# FRONT_PL.net
KiCad netlist of a schematic drawn in Altium Designer
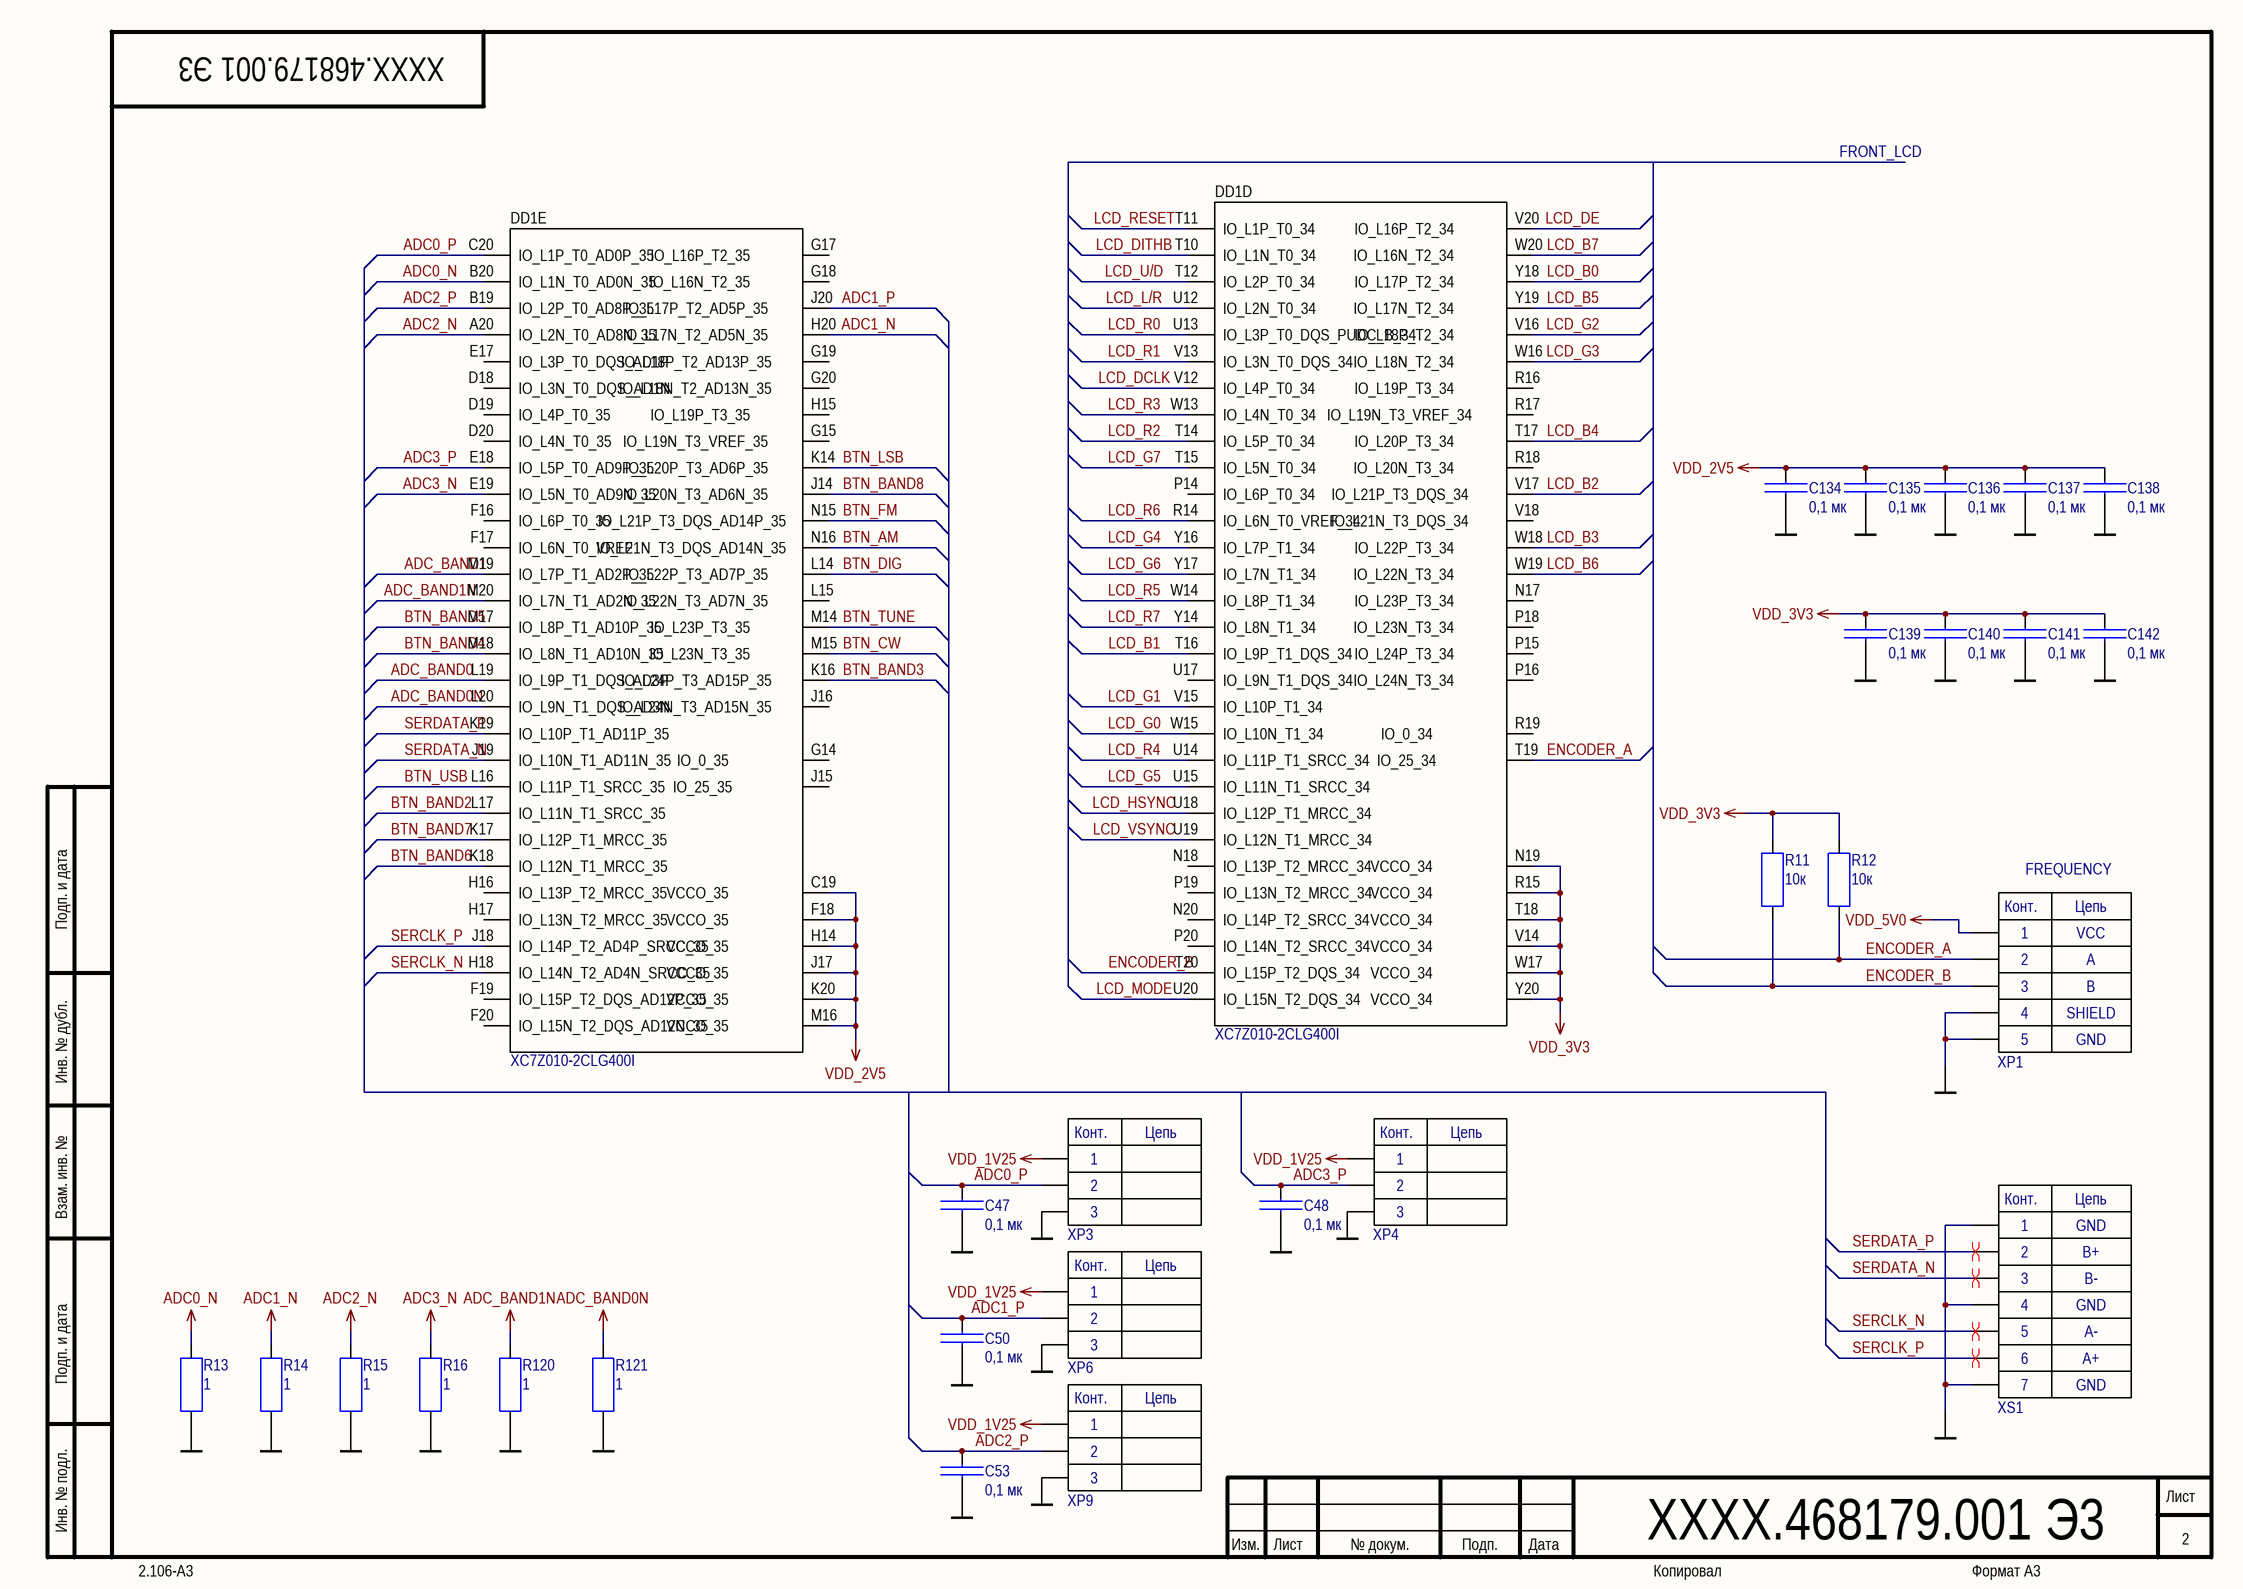
[diagram p0: FRONT_PL.SchDoc]

(export (version "E")
  (design (tool "Eeschema 10.0.6"))
  (components
    (comp (ref "C47")
      (value "CC0402KRX5R6BB104")
      (footprint "CAPC1005X05L")
      (description "ЧИП конденсатор")
      (fields
        (field (name "NOMINAL") "0,1 мк")
        (field (name "MANUFACTURER") "Yageo")
        (field (name "TOLERANCE") "10%")
      )
      (libsource (lib "Database_Gost") (part "Capacitor const"))
    )
    (comp (ref "C48")
      (value "CC0402KRX5R6BB104")
      (footprint "CAPC1005X05L")
      (description "ЧИП конденсатор")
      (fields
        (field (name "NOMINAL") "0,1 мк")
        (field (name "MANUFACTURER") "Yageo")
        (field (name "TOLERANCE") "10%")
      )
      (libsource (lib "Database_Gost") (part "Capacitor const"))
    )
    (comp (ref "C50")
      (value "CC0402KRX5R6BB104")
      (footprint "CAPC1005X05L")
      (description "ЧИП конденсатор")
      (fields
        (field (name "NOMINAL") "0,1 мк")
        (field (name "MANUFACTURER") "Yageo")
        (field (name "TOLERANCE") "10%")
      )
      (libsource (lib "Database_Gost") (part "Capacitor const"))
    )
    (comp (ref "C53")
      (value "CC0402KRX5R6BB104")
      (footprint "CAPC1005X05L")
      (description "ЧИП конденсатор")
      (fields
        (field (name "NOMINAL") "0,1 мк")
        (field (name "MANUFACTURER") "Yageo")
        (field (name "TOLERANCE") "10%")
      )
      (libsource (lib "Database_Gost") (part "Capacitor const"))
    )
    (comp (ref "C134")
      (value "CC0402KRX5R6BB104")
      (footprint "CAPC1005X05L")
      (description "ЧИП конденсатор")
      (fields
        (field (name "NOMINAL") "0,1 мк")
        (field (name "MANUFACTURER") "Yageo")
        (field (name "TOLERANCE") "10%")
      )
      (libsource (lib "Database_Gost") (part "Capacitor const"))
    )
    (comp (ref "C135")
      (value "CC0402KRX5R6BB104")
      (footprint "CAPC1005X05L")
      (description "ЧИП конденсатор")
      (fields
        (field (name "NOMINAL") "0,1 мк")
        (field (name "MANUFACTURER") "Yageo")
        (field (name "TOLERANCE") "10%")
      )
      (libsource (lib "Database_Gost") (part "Capacitor const"))
    )
    (comp (ref "C136")
      (value "CC0402KRX5R6BB104")
      (footprint "CAPC1005X05L")
      (description "ЧИП конденсатор")
      (fields
        (field (name "NOMINAL") "0,1 мк")
        (field (name "MANUFACTURER") "Yageo")
        (field (name "TOLERANCE") "10%")
      )
      (libsource (lib "Database_Gost") (part "Capacitor const"))
    )
    (comp (ref "C137")
      (value "CC0402KRX5R6BB104")
      (footprint "CAPC1005X05L")
      (description "ЧИП конденсатор")
      (fields
        (field (name "NOMINAL") "0,1 мк")
        (field (name "MANUFACTURER") "Yageo")
        (field (name "TOLERANCE") "10%")
      )
      (libsource (lib "Database_Gost") (part "Capacitor const"))
    )
    (comp (ref "C138")
      (value "CC0402KRX5R6BB104")
      (footprint "CAPC1005X05L")
      (description "ЧИП конденсатор")
      (fields
        (field (name "NOMINAL") "0,1 мк")
        (field (name "MANUFACTURER") "Yageo")
        (field (name "TOLERANCE") "10%")
      )
      (libsource (lib "Database_Gost") (part "Capacitor const"))
    )
    (comp (ref "C139")
      (value "CC0402KRX5R6BB104")
      (footprint "CAPC1005X05L")
      (description "ЧИП конденсатор")
      (fields
        (field (name "NOMINAL") "0,1 мк")
        (field (name "MANUFACTURER") "Yageo")
        (field (name "TOLERANCE") "10%")
      )
      (libsource (lib "Database_Gost") (part "Capacitor const"))
    )
    (comp (ref "C140")
      (value "CC0402KRX5R6BB104")
      (footprint "CAPC1005X05L")
      (description "ЧИП конденсатор")
      (fields
        (field (name "NOMINAL") "0,1 мк")
        (field (name "MANUFACTURER") "Yageo")
        (field (name "TOLERANCE") "10%")
      )
      (libsource (lib "Database_Gost") (part "Capacitor const"))
    )
    (comp (ref "C141")
      (value "CC0402KRX5R6BB104")
      (footprint "CAPC1005X05L")
      (description "ЧИП конденсатор")
      (fields
        (field (name "NOMINAL") "0,1 мк")
        (field (name "MANUFACTURER") "Yageo")
        (field (name "TOLERANCE") "10%")
      )
      (libsource (lib "Database_Gost") (part "Capacitor const"))
    )
    (comp (ref "C142")
      (value "CC0402KRX5R6BB104")
      (footprint "CAPC1005X05L")
      (description "ЧИП конденсатор")
      (fields
        (field (name "NOMINAL") "0,1 мк")
        (field (name "MANUFACTURER") "Yageo")
        (field (name "TOLERANCE") "10%")
      )
      (libsource (lib "Database_Gost") (part "Capacitor const"))
    )
    (comp (ref "DD1")
      (value "XC7Z010-2CLG400I")
      (footprint "BGA400C80P20X20_1700X1700X147")
      (description "Zynq®-7000 SoC Family")
      (fields (field (name "MANUFACTURER") "Xilinx"))
      (libsource (lib "Chips_single") (part "XC7Z010-2CLG400I"))
    )
    (comp (ref "R11")
      (value "RC0402JR-0710KL")
      (footprint "RESC1005X04L")
      (description "ЧИП резистор")
      (fields
        (field (name "NOMINAL") "10к")
        (field (name "MANUFACTURER") "Yageo")
        (field (name "TOLERANCE") "5%")
      )
      (libsource (lib "Database_Gost") (part "Resistor const"))
    )
    (comp (ref "R12")
      (value "RC0402JR-0710KL")
      (footprint "RESC1005X04L")
      (description "ЧИП резистор")
      (fields
        (field (name "NOMINAL") "10к")
        (field (name "MANUFACTURER") "Yageo")
        (field (name "TOLERANCE") "5%")
      )
      (libsource (lib "Database_Gost") (part "Resistor const"))
    )
    (comp (ref "R13")
      (value "RC0402JR-071RL")
      (footprint "RESC1005X04L")
      (description "ЧИП резистор")
      (fields
        (field (name "NOMINAL") "1")
        (field (name "MANUFACTURER") "Yageo")
        (field (name "TOLERANCE") "5%")
      )
      (libsource (lib "Database_Gost") (part "Resistor const"))
    )
    (comp (ref "R14")
      (value "RC0402JR-071RL")
      (footprint "RESC1005X04L")
      (description "ЧИП резистор")
      (fields
        (field (name "NOMINAL") "1")
        (field (name "MANUFACTURER") "Yageo")
        (field (name "TOLERANCE") "5%")
      )
      (libsource (lib "Database_Gost") (part "Resistor const"))
    )
    (comp (ref "R15")
      (value "RC0402JR-071RL")
      (footprint "RESC1005X04L")
      (description "ЧИП резистор")
      (fields
        (field (name "NOMINAL") "1")
        (field (name "MANUFACTURER") "Yageo")
        (field (name "TOLERANCE") "5%")
      )
      (libsource (lib "Database_Gost") (part "Resistor const"))
    )
    (comp (ref "R16")
      (value "RC0402JR-071RL")
      (footprint "RESC1005X04L")
      (description "ЧИП резистор")
      (fields
        (field (name "NOMINAL") "1")
        (field (name "MANUFACTURER") "Yageo")
        (field (name "TOLERANCE") "5%")
      )
      (libsource (lib "Database_Gost") (part "Resistor const"))
    )
    (comp (ref "R120")
      (value "RC0402JR-071RL")
      (footprint "RESC1005X04L")
      (description "ЧИП резистор")
      (fields
        (field (name "NOMINAL") "1")
        (field (name "MANUFACTURER") "Yageo")
        (field (name "TOLERANCE") "5%")
      )
      (libsource (lib "Database_Gost") (part "Resistor const"))
    )
    (comp (ref "R121")
      (value "RC0402JR-071RL")
      (footprint "RESC1005X04L")
      (description "ЧИП резистор")
      (fields
        (field (name "NOMINAL") "1")
        (field (name "MANUFACTURER") "Yageo")
        (field (name "TOLERANCE") "5%")
      )
      (libsource (lib "Database_Gost") (part "Resistor const"))
    )
    (comp (ref "XP1")
      (value "WB-05")
      (footprint "WB-05 (MW-5M) pitch 2.00mm")
      (description "WB-05 (MW-5M) pitch 2.00mm\r\nDS1066-05M")
      (libsource (lib "Connectors") (part "WB-05"))
    )
    (comp (ref "XP3")
      (value "WB-03")
      (footprint "WB-03 (MW-3M) PITCH 2.00MM")
      (description "WB-03(MW-3M) pitch 2.00mm\r\nDS1066-03M")
      (libsource (lib "Connectors") (part "WB-03"))
    )
    (comp (ref "XP4")
      (value "WB-03")
      (footprint "WB-03 (MW-3M) PITCH 2.00MM")
      (description "WB-03(MW-3M) pitch 2.00mm\r\nDS1066-03M")
      (libsource (lib "Connectors") (part "WB-03"))
    )
    (comp (ref "XP6")
      (value "WB-03")
      (footprint "WB-03 (MW-3M) PITCH 2.00MM")
      (description "WB-03(MW-3M) pitch 2.00mm\r\nDS1066-03M")
      (libsource (lib "Connectors") (part "WB-03"))
    )
    (comp (ref "XP9")
      (value "WB-03")
      (footprint "WB-03 (MW-3M) PITCH 2.00MM")
      (description "WB-03(MW-3M) pitch 2.00mm\r\nDS1066-03M")
      (libsource (lib "Connectors") (part "WB-03"))
    )
    (comp (ref "XS1")
      (value "KLS1-SATA001")
      (footprint "KLS1-SATA001")
      (description "SATA Type A 7P Male Connector,SMD")
      (libsource (lib "Connectors") (part "SATA KLS1-SATA001"))
    )
  )
  (nets
    (net (code "1") (name "/ADC0_P") (class "Default")
      (node (ref "C47") (pin "2") (pinfunction "2_2") (pintype "passive"))
      (node (ref "DD1") (pin "C20") (pinfunction "IO_L1P_T0_AD0P_35_C20") (pintype "passive"))
      (node (ref "XP3") (pin "2") (pinfunction "2_2") (pintype "passive"))
    )
    (net (code "2") (name "/ADC1_P") (class "Default")
      (node (ref "C50") (pin "2") (pinfunction "2_2") (pintype "passive"))
      (node (ref "DD1") (pin "J20") (pinfunction "IO_L17P_T2_AD5P_35_J20") (pintype "passive"))
      (node (ref "XP6") (pin "2") (pinfunction "2_2") (pintype "passive"))
    )
    (net (code "3") (name "/ADC2_P") (class "Default")
      (node (ref "C53") (pin "2") (pinfunction "2_2") (pintype "passive"))
      (node (ref "DD1") (pin "B19") (pinfunction "IO_L2P_T0_AD8P_35_B19") (pintype "passive"))
      (node (ref "XP9") (pin "2") (pinfunction "2_2") (pintype "passive"))
    )
    (net (code "4") (name "/ADC3_P") (class "Default")
      (node (ref "C48") (pin "2") (pinfunction "2_2") (pintype "passive"))
      (node (ref "DD1") (pin "E18") (pinfunction "IO_L5P_T0_AD9P_35_E18") (pintype "passive"))
      (node (ref "XP4") (pin "2") (pinfunction "2_2") (pintype "passive"))
    )
    (net (code "5") (name "/ADC_BAND0") (class "Default")
      (node (ref "DD1") (pin "L19") (pinfunction "IO_L9P_T1_DQS_AD3P_L19") (pintype "passive"))
    )
    (net (code "6") (name "/ADC_BAND1") (class "Default")
      (node (ref "DD1") (pin "M19") (pinfunction "IO_L7P_T1_AD2P_35_M19") (pintype "passive"))
    )
    (net (code "7") (name "/BTN_AM") (class "Default")
      (node (ref "DD1") (pin "N16") (pinfunction "IO_L21N_T3_DQS_AD14N_35_N16") (pintype "passive"))
    )
    (net (code "8") (name "/BTN_BAND2") (class "Default")
      (node (ref "DD1") (pin "L17") (pinfunction "IO_L11N_T1_SRCC_35_L17") (pintype "passive"))
    )
    (net (code "9") (name "/BTN_BAND3") (class "Default")
      (node (ref "DD1") (pin "K16") (pinfunction "IO_L24P_T3_AD15P_35_K16") (pintype "passive"))
    )
    (net (code "10") (name "/BTN_BAND4") (class "Default")
      (node (ref "DD1") (pin "M18") (pinfunction "IO_L8N_T1_AD10N_35_M18") (pintype "passive"))
    )
    (net (code "11") (name "/BTN_BAND5") (class "Default")
      (node (ref "DD1") (pin "M17") (pinfunction "IO_L8P_T1_AD10P_35_M17") (pintype "passive"))
    )
    (net (code "12") (name "/BTN_BAND6") (class "Default")
      (node (ref "DD1") (pin "K18") (pinfunction "IO_L12N_T1_MRCC_35_K18") (pintype "passive"))
    )
    (net (code "13") (name "/BTN_BAND7") (class "Default")
      (node (ref "DD1") (pin "K17") (pinfunction "IO_L12P_T1_MRCC_35_K17") (pintype "passive"))
    )
    (net (code "14") (name "/BTN_BAND8") (class "Default")
      (node (ref "DD1") (pin "J14") (pinfunction "IO_L20N_T3_AD6N_35_J14") (pintype "passive"))
    )
    (net (code "15") (name "/BTN_CW") (class "Default")
      (node (ref "DD1") (pin "M15") (pinfunction "IO_L23N_T3_35_M15") (pintype "passive"))
    )
    (net (code "16") (name "/BTN_DIG") (class "Default")
      (node (ref "DD1") (pin "L14") (pinfunction "IO_L22P_T3_AD7P_35_L14") (pintype "passive"))
    )
    (net (code "17") (name "/BTN_FM") (class "Default")
      (node (ref "DD1") (pin "N15") (pinfunction "IO_L21P_T3_DQS_AD14P_35_N15") (pintype "passive"))
    )
    (net (code "18") (name "/BTN_LSB") (class "Default")
      (node (ref "DD1") (pin "K14") (pinfunction "IO_L20P_T3_AD6P_35_K14") (pintype "passive"))
    )
    (net (code "19") (name "/BTN_TUNE") (class "Default")
      (node (ref "DD1") (pin "M14") (pinfunction "IO_L23P_T3_35_M14") (pintype "passive"))
    )
    (net (code "20") (name "/BTN_USB") (class "Default")
      (node (ref "DD1") (pin "L16") (pinfunction "IO_L11P_T1_SRCC_35_L16") (pintype "passive"))
    )
    (net (code "21") (name "/ENCODER_A") (class "Default")
      (node (ref "DD1") (pin "T19") (pinfunction "IO_25_34_T19") (pintype "open_collector"))
      (node (ref "R12") (pin "2") (pinfunction "2_2") (pintype "passive"))
      (node (ref "XP1") (pin "2") (pinfunction "2_2") (pintype "passive"))
    )
    (net (code "22") (name "/ENCODER_B") (class "Default")
      (node (ref "DD1") (pin "T20") (pinfunction "IO_L15P_T2_DQS_34_T20") (pintype "open_collector"))
      (node (ref "R11") (pin "2") (pinfunction "2_2") (pintype "passive"))
      (node (ref "XP1") (pin "3") (pinfunction "3_3") (pintype "passive"))
    )
    (net (code "23") (name "/LCD_B0") (class "Default")
      (node (ref "DD1") (pin "Y18") (pinfunction "IO_L17P_T2_34_Y18") (pintype "open_collector"))
    )
    (net (code "24") (name "/LCD_B1") (class "Default")
      (node (ref "DD1") (pin "T16") (pinfunction "IO_L9P_T1_DQS_34_T16") (pintype "open_collector"))
    )
    (net (code "25") (name "/LCD_B2") (class "Default")
      (node (ref "DD1") (pin "V17") (pinfunction "IO_L21P_T3_DQS_34_V17") (pintype "open_collector"))
    )
    (net (code "26") (name "/LCD_B3") (class "Default")
      (node (ref "DD1") (pin "W18") (pinfunction "IO_L22P_T3_34_W18") (pintype "open_collector"))
    )
    (net (code "27") (name "/LCD_B4") (class "Default")
      (node (ref "DD1") (pin "T17") (pinfunction "IO_L20P_T3_34_T17") (pintype "open_collector"))
    )
    (net (code "28") (name "/LCD_B5") (class "Default")
      (node (ref "DD1") (pin "Y19") (pinfunction "IO_L17N_T2_34_Y19") (pintype "open_collector"))
    )
    (net (code "29") (name "/LCD_B6") (class "Default")
      (node (ref "DD1") (pin "W19") (pinfunction "IO_L22N_T3_34_W19") (pintype "open_collector"))
    )
    (net (code "30") (name "/LCD_B7") (class "Default")
      (node (ref "DD1") (pin "W20") (pinfunction "IO_L16N_T2_34_W20") (pintype "open_collector"))
    )
    (net (code "31") (name "/LCD_DCLK") (class "Default")
      (node (ref "DD1") (pin "V12") (pinfunction "IO_L4P_T0_34_V12") (pintype "open_collector"))
    )
    (net (code "32") (name "/LCD_DE") (class "Default")
      (node (ref "DD1") (pin "V20") (pinfunction "IO_L16P_T2_34_V20") (pintype "open_collector"))
    )
    (net (code "33") (name "/LCD_DITHB") (class "Default")
      (node (ref "DD1") (pin "T10") (pinfunction "IO_L1N_T0_34_T10") (pintype "open_collector"))
    )
    (net (code "34") (name "/LCD_G0") (class "Default")
      (node (ref "DD1") (pin "W15") (pinfunction "IO_L10N_T1_34_W15") (pintype "open_collector"))
    )
    (net (code "35") (name "/LCD_G1") (class "Default")
      (node (ref "DD1") (pin "V15") (pinfunction "IO_L10P_T1_34_V15") (pintype "open_collector"))
    )
    (net (code "36") (name "/LCD_G2") (class "Default")
      (node (ref "DD1") (pin "V16") (pinfunction "IO_L18P_T2_34_V16") (pintype "open_collector"))
    )
    (net (code "37") (name "/LCD_G3") (class "Default")
      (node (ref "DD1") (pin "W16") (pinfunction "IO_L18N_T2_34_W16") (pintype "open_collector"))
    )
    (net (code "38") (name "/LCD_G4") (class "Default")
      (node (ref "DD1") (pin "Y16") (pinfunction "IO_L7P_T1_34_Y16") (pintype "open_collector"))
    )
    (net (code "39") (name "/LCD_G5") (class "Default")
      (node (ref "DD1") (pin "U15") (pinfunction "IO_L11N_T1_SRCC_34_U15") (pintype "open_collector"))
    )
    (net (code "40") (name "/LCD_G6") (class "Default")
      (node (ref "DD1") (pin "Y17") (pinfunction "IO_L7N_T1_34_Y17") (pintype "open_collector"))
    )
    (net (code "41") (name "/LCD_G7") (class "Default")
      (node (ref "DD1") (pin "T15") (pinfunction "IO_L5N_T0_34_T15") (pintype "open_collector"))
    )
    (net (code "42") (name "/LCD_HSYNC") (class "Default")
      (node (ref "DD1") (pin "U18") (pinfunction "IO_L12P_T1_MRCC_34_U18") (pintype "open_collector"))
    )
    (net (code "43") (name "/LCD_L{slash}R") (class "Default")
      (node (ref "DD1") (pin "U12") (pinfunction "IO_L2N_T0_34_U12") (pintype "open_collector"))
    )
    (net (code "44") (name "/LCD_MODE") (class "Default")
      (node (ref "DD1") (pin "U20") (pinfunction "IO_L15N_T2_DQS_34_U20") (pintype "open_collector"))
    )
    (net (code "45") (name "/LCD_R0") (class "Default")
      (node (ref "DD1") (pin "U13") (pinfunction "IO_L3P_T0_DQS_PUDC_B_34_U13") (pintype "open_collector"))
    )
    (net (code "46") (name "/LCD_R1") (class "Default")
      (node (ref "DD1") (pin "V13") (pinfunction "IO_L3N_T0_DQS_34_V13") (pintype "open_collector"))
    )
    (net (code "47") (name "/LCD_R2") (class "Default")
      (node (ref "DD1") (pin "T14") (pinfunction "IO_L5P_T0_34_T14") (pintype "open_collector"))
    )
    (net (code "48") (name "/LCD_R3") (class "Default")
      (node (ref "DD1") (pin "W13") (pinfunction "IO_L4N_T0_34_W13") (pintype "open_collector"))
    )
    (net (code "49") (name "/LCD_R4") (class "Default")
      (node (ref "DD1") (pin "U14") (pinfunction "IO_L11P_T1_SRCC_34_U14") (pintype "open_collector"))
    )
    (net (code "50") (name "/LCD_R5") (class "Default")
      (node (ref "DD1") (pin "W14") (pinfunction "IO_L8P_T1_34_W14") (pintype "open_collector"))
    )
    (net (code "51") (name "/LCD_R6") (class "Default")
      (node (ref "DD1") (pin "R14") (pinfunction "IO_L6N_T0_VREF_34_R14") (pintype "open_collector"))
    )
    (net (code "52") (name "/LCD_R7") (class "Default")
      (node (ref "DD1") (pin "Y14") (pinfunction "IO_L8N_T1_34_Y14") (pintype "open_collector"))
    )
    (net (code "53") (name "/LCD_RESET") (class "Default")
      (node (ref "DD1") (pin "T11") (pinfunction "IO_L1P_T0_34_T11") (pintype "open_collector"))
    )
    (net (code "54") (name "/LCD_U{slash}D") (class "Default")
      (node (ref "DD1") (pin "T12") (pinfunction "IO_L2P_T0_34_T12") (pintype "open_collector"))
    )
    (net (code "55") (name "/LCD_VSYNC") (class "Default")
      (node (ref "DD1") (pin "U19") (pinfunction "IO_L12N_T1_MRCC_34_U19") (pintype "open_collector"))
    )
    (net (code "56") (name "/SERCLK_N") (class "Default")
      (node (ref "DD1") (pin "H18") (pinfunction "IO_L14N_T2_AD4N_SRCC_35_H18") (pintype "passive"))
      (node (ref "XS1") (pin "5") (pinfunction "5_5") (pintype "passive"))
    )
    (net (code "57") (name "/SERCLK_P") (class "Default")
      (node (ref "DD1") (pin "J18") (pinfunction "IO_L14P_T2_AD4P_SRCC_35_J18") (pintype "passive"))
      (node (ref "XS1") (pin "6") (pinfunction "6_6") (pintype "passive"))
    )
    (net (code "58") (name "/SERDATA_N") (class "Default")
      (node (ref "DD1") (pin "J19") (pinfunction "IO_L10N_T1_AD11N_35_J19") (pintype "passive"))
      (node (ref "XS1") (pin "3") (pinfunction "3_3") (pintype "passive"))
    )
    (net (code "59") (name "/SERDATA_P") (class "Default")
      (node (ref "DD1") (pin "K19") (pinfunction "IO_L10P_T1_AD11P_35_K19") (pintype "passive"))
      (node (ref "XS1") (pin "2") (pinfunction "2_2") (pintype "passive"))
    )
    (net (code "60") (name "ADC0_N") (class "Default")
      (node (ref "DD1") (pin "B20") (pinfunction "IO_L1N_T0_AD0N_35_B20") (pintype "passive"))
      (node (ref "R13") (pin "2") (pinfunction "2_2") (pintype "passive"))
    )
    (net (code "61") (name "ADC1_N") (class "Default")
      (node (ref "DD1") (pin "H20") (pinfunction "IO_L17N_T2_AD5N_35_H20") (pintype "passive"))
      (node (ref "R14") (pin "2") (pinfunction "2_2") (pintype "passive"))
    )
    (net (code "62") (name "ADC2_N") (class "Default")
      (node (ref "DD1") (pin "A20") (pinfunction "IO_L2N_T0_AD8N_35_A20") (pintype "passive"))
      (node (ref "R15") (pin "2") (pinfunction "2_2") (pintype "passive"))
    )
    (net (code "63") (name "ADC3_N") (class "Default")
      (node (ref "DD1") (pin "E19") (pinfunction "IO_L5N_T0_AD9N_35_E19") (pintype "passive"))
      (node (ref "R16") (pin "2") (pinfunction "2_2") (pintype "passive"))
    )
    (net (code "64") (name "ADC_BAND0N") (class "Default")
      (node (ref "DD1") (pin "L20") (pinfunction "IO_L9N_T1_DQS_AD3N_L20") (pintype "passive"))
      (node (ref "R121") (pin "2") (pinfunction "2_2") (pintype "passive"))
    )
    (net (code "65") (name "ADC_BAND1N") (class "Default")
      (node (ref "DD1") (pin "M20") (pinfunction "IO_L7N_T1_AD2N_35_M20") (pintype "passive"))
      (node (ref "R120") (pin "2") (pinfunction "2_2") (pintype "passive"))
    )
    (net (code "66") (name "GND") (class "Default")
      (node (ref "C134") (pin "1") (pinfunction "1_1") (pintype "passive"))
      (node (ref "C135") (pin "1") (pinfunction "1_1") (pintype "passive"))
      (node (ref "C136") (pin "1") (pinfunction "1_1") (pintype "passive"))
      (node (ref "C137") (pin "1") (pinfunction "1_1") (pintype "passive"))
      (node (ref "C138") (pin "1") (pinfunction "1_1") (pintype "passive"))
      (node (ref "C139") (pin "1") (pinfunction "1_1") (pintype "passive"))
      (node (ref "C140") (pin "1") (pinfunction "1_1") (pintype "passive"))
      (node (ref "C141") (pin "1") (pinfunction "1_1") (pintype "passive"))
      (node (ref "C142") (pin "1") (pinfunction "1_1") (pintype "passive"))
      (node (ref "C47") (pin "1") (pinfunction "1_1") (pintype "passive"))
      (node (ref "C48") (pin "1") (pinfunction "1_1") (pintype "passive"))
      (node (ref "C50") (pin "1") (pinfunction "1_1") (pintype "passive"))
      (node (ref "C53") (pin "1") (pinfunction "1_1") (pintype "passive"))
      (node (ref "R120") (pin "1") (pinfunction "1_1") (pintype "passive"))
      (node (ref "R121") (pin "1") (pinfunction "1_1") (pintype "passive"))
      (node (ref "R13") (pin "1") (pinfunction "1_1") (pintype "passive"))
      (node (ref "R14") (pin "1") (pinfunction "1_1") (pintype "passive"))
      (node (ref "R15") (pin "1") (pinfunction "1_1") (pintype "passive"))
      (node (ref "R16") (pin "1") (pinfunction "1_1") (pintype "passive"))
      (node (ref "XP1") (pin "4") (pinfunction "4_4") (pintype "passive"))
      (node (ref "XP1") (pin "5") (pinfunction "5_5") (pintype "passive"))
      (node (ref "XP3") (pin "3") (pinfunction "3_3") (pintype "passive"))
      (node (ref "XP4") (pin "3") (pinfunction "3_3") (pintype "passive"))
      (node (ref "XP6") (pin "3") (pinfunction "3_3") (pintype "passive"))
      (node (ref "XP9") (pin "3") (pinfunction "3_3") (pintype "passive"))
      (node (ref "XS1") (pin "1") (pinfunction "1_1") (pintype "passive"))
      (node (ref "XS1") (pin "4") (pinfunction "4_4") (pintype "passive"))
      (node (ref "XS1") (pin "7") (pinfunction "7_7") (pintype "passive"))
    )
    (net (code "67") (name "VDD_1V25") (class "Default")
      (node (ref "XP3") (pin "1") (pinfunction "1_1") (pintype "passive"))
      (node (ref "XP4") (pin "1") (pinfunction "1_1") (pintype "passive"))
      (node (ref "XP6") (pin "1") (pinfunction "1_1") (pintype "passive"))
      (node (ref "XP9") (pin "1") (pinfunction "1_1") (pintype "passive"))
    )
    (net (code "68") (name "VDD_2V5") (class "Default")
      (node (ref "C134") (pin "2") (pinfunction "2_2") (pintype "passive"))
      (node (ref "C135") (pin "2") (pinfunction "2_2") (pintype "passive"))
      (node (ref "C136") (pin "2") (pinfunction "2_2") (pintype "passive"))
      (node (ref "C137") (pin "2") (pinfunction "2_2") (pintype "passive"))
      (node (ref "C138") (pin "2") (pinfunction "2_2") (pintype "passive"))
      (node (ref "DD1") (pin "C19") (pinfunction "VCCO_35_C19") (pintype "passive"))
      (node (ref "DD1") (pin "F18") (pinfunction "VCCO_35_F18") (pintype "passive"))
      (node (ref "DD1") (pin "H14") (pinfunction "VCCO_35_H14") (pintype "passive"))
      (node (ref "DD1") (pin "J17") (pinfunction "VCCO_35_J17") (pintype "passive"))
      (node (ref "DD1") (pin "K20") (pinfunction "VCCO_35_K20") (pintype "passive"))
      (node (ref "DD1") (pin "M16") (pinfunction "VCCO_35_M16") (pintype "passive"))
    )
    (net (code "69") (name "VDD_3V3") (class "Default")
      (node (ref "C139") (pin "2") (pinfunction "2_2") (pintype "passive"))
      (node (ref "C140") (pin "2") (pinfunction "2_2") (pintype "passive"))
      (node (ref "C141") (pin "2") (pinfunction "2_2") (pintype "passive"))
      (node (ref "C142") (pin "2") (pinfunction "2_2") (pintype "passive"))
      (node (ref "DD1") (pin "N19") (pinfunction "VCCO_34_N19") (pintype "open_collector"))
      (node (ref "DD1") (pin "R15") (pinfunction "VCCO_34_R15") (pintype "open_collector"))
      (node (ref "DD1") (pin "T18") (pinfunction "VCCO_34_T18") (pintype "open_collector"))
      (node (ref "DD1") (pin "V14") (pinfunction "VCCO_34_V14") (pintype "open_collector"))
      (node (ref "DD1") (pin "W17") (pinfunction "VCCO_34_W17") (pintype "open_collector"))
      (node (ref "DD1") (pin "Y20") (pinfunction "VCCO_34_Y20") (pintype "open_collector"))
      (node (ref "R11") (pin "1") (pinfunction "1_1") (pintype "passive"))
      (node (ref "R12") (pin "1") (pinfunction "1_1") (pintype "passive"))
    )
    (net (code "70") (name "VDD_5V0") (class "Default")
      (node (ref "XP1") (pin "1") (pinfunction "1_1") (pintype "passive"))
    )
    (net (code "71") (name "unconnected-(DD1D-IO_0_34-PadR19)") (class "Default")
      (node (ref "DD1") (pin "R19") (pinfunction "IO_0_34_R19") (pintype "open_collector"))
    )
    (net (code "72") (name "unconnected-(DD1D-IO_L6P_T0_34-PadP14)") (class "Default")
      (node (ref "DD1") (pin "P14") (pinfunction "IO_L6P_T0_34_P14") (pintype "open_collector"))
    )
    (net (code "73") (name "unconnected-(DD1D-IO_L9N_T1_DQS_34-PadU17)") (class "Default")
      (node (ref "DD1") (pin "U17") (pinfunction "IO_L9N_T1_DQS_34_U17") (pintype "open_collector"))
    )
    (net (code "74") (name "unconnected-(DD1D-IO_L13N_T2_MRCC_34-PadP19)") (class "Default")
      (node (ref "DD1") (pin "P19") (pinfunction "IO_L13N_T2_MRCC_34_P19") (pintype "open_collector"))
    )
    (net (code "75") (name "unconnected-(DD1D-IO_L13P_T2_MRCC_34-PadN18)") (class "Default")
      (node (ref "DD1") (pin "N18") (pinfunction "IO_L13P_T2_MRCC_34_N18") (pintype "open_collector"))
    )
    (net (code "76") (name "unconnected-(DD1D-IO_L14N_T2_SRCC_34-PadP20)") (class "Default")
      (node (ref "DD1") (pin "P20") (pinfunction "IO_L14N_T2_SRCC_34_P20") (pintype "open_collector"))
    )
    (net (code "77") (name "unconnected-(DD1D-IO_L14P_T2_SRCC_34-PadN20)") (class "Default")
      (node (ref "DD1") (pin "N20") (pinfunction "IO_L14P_T2_SRCC_34_N20") (pintype "open_collector"))
    )
    (net (code "78") (name "unconnected-(DD1D-IO_L19N_T3_VREF_34-PadR17)") (class "Default")
      (node (ref "DD1") (pin "R17") (pinfunction "IO_L19N_T3_VREF_34_R17") (pintype "open_collector"))
    )
    (net (code "79") (name "unconnected-(DD1D-IO_L19P_T3_34-PadR16)") (class "Default")
      (node (ref "DD1") (pin "R16") (pinfunction "IO_L19P_T3_34_R16") (pintype "open_collector"))
    )
    (net (code "80") (name "unconnected-(DD1D-IO_L20N_T3_34-PadR18)") (class "Default")
      (node (ref "DD1") (pin "R18") (pinfunction "IO_L20N_T3_34_R18") (pintype "open_collector"))
    )
    (net (code "81") (name "unconnected-(DD1D-IO_L21N_T3_DQS_34-PadV18)") (class "Default")
      (node (ref "DD1") (pin "V18") (pinfunction "IO_L21N_T3_DQS_34_V18") (pintype "open_collector"))
    )
    (net (code "82") (name "unconnected-(DD1D-IO_L23N_T3_34-PadP18)") (class "Default")
      (node (ref "DD1") (pin "P18") (pinfunction "IO_L23N_T3_34_P18") (pintype "open_collector"))
    )
    (net (code "83") (name "unconnected-(DD1D-IO_L23P_T3_34-PadN17)") (class "Default")
      (node (ref "DD1") (pin "N17") (pinfunction "IO_L23P_T3_34_N17") (pintype "open_collector"))
    )
    (net (code "84") (name "unconnected-(DD1D-IO_L24N_T3_34-PadP16)") (class "Default")
      (node (ref "DD1") (pin "P16") (pinfunction "IO_L24N_T3_34_P16") (pintype "open_collector"))
    )
    (net (code "85") (name "unconnected-(DD1D-IO_L24P_T3_34-PadP15)") (class "Default")
      (node (ref "DD1") (pin "P15") (pinfunction "IO_L24P_T3_34_P15") (pintype "open_collector"))
    )
    (net (code "86") (name "unconnected-(DD1E-IO_0_35-PadG14)") (class "Default")
      (node (ref "DD1") (pin "G14") (pinfunction "IO_0_35_G14") (pintype "passive"))
    )
    (net (code "87") (name "unconnected-(DD1E-IO_25_35-PadJ15)") (class "Default")
      (node (ref "DD1") (pin "J15") (pinfunction "IO_25_35_J15") (pintype "passive"))
    )
    (net (code "88") (name "unconnected-(DD1E-IO_L3N_T0_DQS_AD1N-PadD18)") (class "Default")
      (node (ref "DD1") (pin "D18") (pinfunction "IO_L3N_T0_DQS_AD1N_D18") (pintype "passive"))
    )
    (net (code "89") (name "unconnected-(DD1E-IO_L3P_T0_DQS_AD1P-PadE17)") (class "Default")
      (node (ref "DD1") (pin "E17") (pinfunction "IO_L3P_T0_DQS_AD1P_E17") (pintype "passive"))
    )
    (net (code "90") (name "unconnected-(DD1E-IO_L4N_T0_35-PadD20)") (class "Default")
      (node (ref "DD1") (pin "D20") (pinfunction "IO_L4N_T0_35_D20") (pintype "passive"))
    )
    (net (code "91") (name "unconnected-(DD1E-IO_L4P_T0_35-PadD19)") (class "Default")
      (node (ref "DD1") (pin "D19") (pinfunction "IO_L4P_T0_35_D19") (pintype "passive"))
    )
    (net (code "92") (name "unconnected-(DD1E-IO_L6N_T0_VREF-PadF17)") (class "Default")
      (node (ref "DD1") (pin "F17") (pinfunction "IO_L6N_T0_VREF_F17") (pintype "passive"))
    )
    (net (code "93") (name "unconnected-(DD1E-IO_L6P_T0_35-PadF16)") (class "Default")
      (node (ref "DD1") (pin "F16") (pinfunction "IO_L6P_T0_35_F16") (pintype "passive"))
    )
    (net (code "94") (name "unconnected-(DD1E-IO_L13N_T2_MRCC_35-PadH17)") (class "Default")
      (node (ref "DD1") (pin "H17") (pinfunction "IO_L13N_T2_MRCC_35_H17") (pintype "passive"))
    )
    (net (code "95") (name "unconnected-(DD1E-IO_L13P_T2_MRCC_35-PadH16)") (class "Default")
      (node (ref "DD1") (pin "H16") (pinfunction "IO_L13P_T2_MRCC_35_H16") (pintype "passive"))
    )
    (net (code "96") (name "unconnected-(DD1E-IO_L15N_T2_DQS_AD12N_35-PadF20)") (class "Default")
      (node (ref "DD1") (pin "F20") (pinfunction "IO_L15N_T2_DQS_AD12N_35_F20") (pintype "passive"))
    )
    (net (code "97") (name "unconnected-(DD1E-IO_L15P_T2_DQS_AD12P_35-PadF19)") (class "Default")
      (node (ref "DD1") (pin "F19") (pinfunction "IO_L15P_T2_DQS_AD12P_35_F19") (pintype "passive"))
    )
    (net (code "98") (name "unconnected-(DD1E-IO_L16N_T2_35-PadG18)") (class "Default")
      (node (ref "DD1") (pin "G18") (pinfunction "IO_L16N_T2_35_G18") (pintype "passive"))
    )
    (net (code "99") (name "unconnected-(DD1E-IO_L16P_T2_35-PadG17)") (class "Default")
      (node (ref "DD1") (pin "G17") (pinfunction "IO_L16P_T2_35_G17") (pintype "passive"))
    )
    (net (code "100") (name "unconnected-(DD1E-IO_L18N_T2_AD13N_35-PadG20)") (class "Default")
      (node (ref "DD1") (pin "G20") (pinfunction "IO_L18N_T2_AD13N_35_G20") (pintype "passive"))
    )
    (net (code "101") (name "unconnected-(DD1E-IO_L18P_T2_AD13P_35-PadG19)") (class "Default")
      (node (ref "DD1") (pin "G19") (pinfunction "IO_L18P_T2_AD13P_35_G19") (pintype "passive"))
    )
    (net (code "102") (name "unconnected-(DD1E-IO_L19N_T3_VREF_35-PadG15)") (class "Default")
      (node (ref "DD1") (pin "G15") (pinfunction "IO_L19N_T3_VREF_35_G15") (pintype "passive"))
    )
    (net (code "103") (name "unconnected-(DD1E-IO_L19P_T3_35-PadH15)") (class "Default")
      (node (ref "DD1") (pin "H15") (pinfunction "IO_L19P_T3_35_H15") (pintype "passive"))
    )
    (net (code "104") (name "unconnected-(DD1E-IO_L22N_T3_AD7N_35-PadL15)") (class "Default")
      (node (ref "DD1") (pin "L15") (pinfunction "IO_L22N_T3_AD7N_35_L15") (pintype "passive"))
    )
    (net (code "105") (name "unconnected-(DD1E-IO_L24N_T3_AD15N_35-PadJ16)") (class "Default")
      (node (ref "DD1") (pin "J16") (pinfunction "IO_L24N_T3_AD15N_35_J16") (pintype "passive"))
    )
  )
)
